# attiny.net
KiCad netlist of a schematic drawn in EAGLE
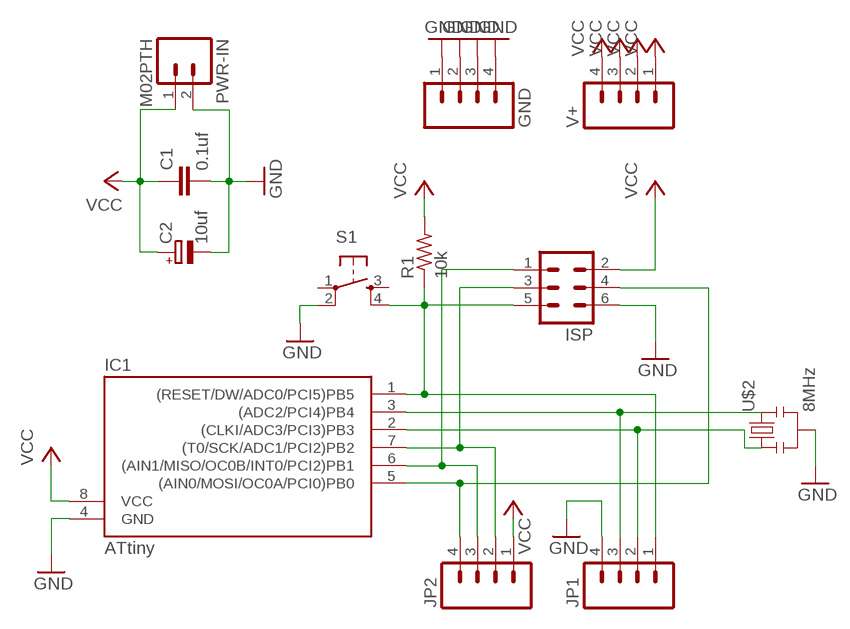
[diagram p0: schematic, sheet 1]

(export (version "E")
  (design (tool "Eeschema 10.0.6"))
  (components
    (comp (ref "C1")
      (value "0.1uf")
      (footprint "eagle-import:C025-025X050")
      (libsource (lib "eagle-import") (part "C-EU025-025X050"))
    )
    (comp (ref "C2")
      (value "10uf")
      (footprint "eagle-import:E2-4")
      (libsource (lib "eagle-import") (part "CPOL-EUE2-4"))
    )
    (comp (ref "GND")
      (value "M04PTH")
      (footprint "eagle-import:1X04")
      (libsource (lib "eagle-import") (part "M04PTH"))
    )
    (comp (ref "IC1")
      (value "ATtiny")
      (footprint "eagle-import:DIL08")
      (libsource (lib "eagle-import") (part "ATTINY13P-20"))
    )
    (comp (ref "ISP")
      (value "MA03-2")
      (footprint "eagle-import:MA03-2")
      (libsource (lib "eagle-import") (part "MA03-2"))
    )
    (comp (ref "JP1")
      (value "M04PTH")
      (footprint "eagle-import:1X04")
      (libsource (lib "eagle-import") (part "M04PTH"))
    )
    (comp (ref "JP2")
      (value "M04PTH")
      (footprint "eagle-import:1X04")
      (libsource (lib "eagle-import") (part "M04PTH"))
    )
    (comp (ref "PWR-IN")
      (value "M02PTH")
      (footprint "eagle-import:1X02")
      (libsource (lib "eagle-import") (part "M02PTH"))
    )
    (comp (ref "R1")
      (value "10k")
      (footprint "eagle-import:0204_7")
      (libsource (lib "eagle-import") (part "R-US_0204/7"))
    )
    (comp (ref "S1")
      (value "TAC_SWITCHPTH")
      (footprint "eagle-import:TACTILE-PTH")
      (libsource (lib "eagle-import") (part "TAC_SWITCHPTH"))
    )
    (comp (ref "U$2")
      (value "8MHz")
      (footprint "eagle-import:RESONATOR-PTH")
      (libsource (lib "eagle-import") (part "RESONATORPTH"))
    )
    (comp (ref "V+")
      (value "M04PTH")
      (footprint "eagle-import:1X04")
      (libsource (lib "eagle-import") (part "M04PTH"))
    )
  )
  (nets
    (net (code "1") (name "GND") (class "Default")
      (node (ref "C1") (pin "2") (pinfunction "2_2") (pintype "passive"))
      (node (ref "C2") (pin "-") (pinfunction "-_-") (pintype "passive"))
      (node (ref "GND") (pin "1") (pinfunction "1_1") (pintype "passive"))
      (node (ref "GND") (pin "2") (pinfunction "2_2") (pintype "passive"))
      (node (ref "GND") (pin "3") (pinfunction "3_3") (pintype "passive"))
      (node (ref "GND") (pin "4") (pinfunction "4_4") (pintype "passive"))
      (node (ref "IC1") (pin "4") (pinfunction "GND_4") (pintype "power_in"))
      (node (ref "ISP") (pin "6") (pinfunction "6_6") (pintype "passive"))
      (node (ref "JP1") (pin "4") (pinfunction "4_4") (pintype "passive"))
      (node (ref "PWR-IN") (pin "2") (pinfunction "2_2") (pintype "passive"))
      (node (ref "S1") (pin "2") (pinfunction "2_2") (pintype "passive"))
      (node (ref "U$2") (pin "2") (pinfunction "2_2") (pintype "passive"))
    )
    (net (code "2") (name "Net-(IC1-(ADC2{slash}PCI4)PB4)") (class "Default")
      (node (ref "IC1") (pin "3") (pinfunction "(ADC2/PCI4)PB4_3") (pintype "bidirectional"))
      (node (ref "JP1") (pin "3") (pinfunction "3_3") (pintype "passive"))
      (node (ref "U$2") (pin "3") (pinfunction "3_3") (pintype "passive"))
    )
    (net (code "3") (name "Net-(IC1-(AIN0{slash}MOSI{slash}OC0A{slash}PCI0)PB0)") (class "Default")
      (node (ref "IC1") (pin "5") (pinfunction "(AIN0/MOSI/OC0A/PCI0)PB0_5") (pintype "bidirectional"))
      (node (ref "ISP") (pin "4") (pinfunction "4_4") (pintype "passive"))
      (node (ref "JP2") (pin "4") (pinfunction "4_4") (pintype "passive"))
    )
    (net (code "4") (name "Net-(IC1-(AIN1{slash}MISO{slash}OC0B{slash}INT0{slash}PCI2)PB1)") (class "Default")
      (node (ref "IC1") (pin "6") (pinfunction "(AIN1/MISO/OC0B/INT0/PCI2)PB1_6") (pintype "bidirectional"))
      (node (ref "ISP") (pin "1") (pinfunction "1_1") (pintype "passive"))
      (node (ref "JP2") (pin "3") (pinfunction "3_3") (pintype "passive"))
    )
    (net (code "5") (name "Net-(IC1-(CLKI{slash}ADC3{slash}PCI3)PB3)") (class "Default")
      (node (ref "IC1") (pin "2") (pinfunction "(CLKI/ADC3/PCI3)PB3_2") (pintype "bidirectional"))
      (node (ref "JP1") (pin "2") (pinfunction "2_2") (pintype "passive"))
      (node (ref "U$2") (pin "1") (pinfunction "1_1") (pintype "passive"))
    )
    (net (code "6") (name "Net-(IC1-(RESET{slash}DW{slash}ADC0{slash}PCI5)PB5)") (class "Default")
      (node (ref "IC1") (pin "1") (pinfunction "(RESET/DW/ADC0/PCI5)PB5_1") (pintype "bidirectional"))
      (node (ref "ISP") (pin "5") (pinfunction "5_5") (pintype "passive"))
      (node (ref "JP1") (pin "1") (pinfunction "1_1") (pintype "passive"))
      (node (ref "R1") (pin "1") (pinfunction "1_1") (pintype "passive"))
      (node (ref "S1") (pin "4") (pinfunction "4_4") (pintype "passive"))
    )
    (net (code "7") (name "Net-(IC1-(T0{slash}SCK{slash}ADC1{slash}PCI2)PB2)") (class "Default")
      (node (ref "IC1") (pin "7") (pinfunction "(T0/SCK/ADC1/PCI2)PB2_7") (pintype "bidirectional"))
      (node (ref "ISP") (pin "3") (pinfunction "3_3") (pintype "passive"))
      (node (ref "JP2") (pin "2") (pinfunction "2_2") (pintype "passive"))
    )
    (net (code "8") (name "VCC") (class "Default")
      (node (ref "C1") (pin "1") (pinfunction "1_1") (pintype "passive"))
      (node (ref "C2") (pin "+") (pinfunction "+_+") (pintype "passive"))
      (node (ref "IC1") (pin "8") (pinfunction "VCC_8") (pintype "power_in"))
      (node (ref "ISP") (pin "2") (pinfunction "2_2") (pintype "passive"))
      (node (ref "JP2") (pin "1") (pinfunction "1_1") (pintype "passive"))
      (node (ref "PWR-IN") (pin "1") (pinfunction "1_1") (pintype "passive"))
      (node (ref "R1") (pin "2") (pinfunction "2_2") (pintype "passive"))
      (node (ref "V+") (pin "1") (pinfunction "1_1") (pintype "passive"))
      (node (ref "V+") (pin "2") (pinfunction "2_2") (pintype "passive"))
      (node (ref "V+") (pin "3") (pinfunction "3_3") (pintype "passive"))
      (node (ref "V+") (pin "4") (pinfunction "4_4") (pintype "passive"))
    )
    (net (code "9") (name "unconnected-(S1-Pad1)") (class "Default")
      (node (ref "S1") (pin "1") (pinfunction "1_1") (pintype "passive"))
    )
    (net (code "10") (name "unconnected-(S1-Pad3)") (class "Default")
      (node (ref "S1") (pin "3") (pinfunction "3_3") (pintype "passive"))
    )
  )
)
